# SSD1306_v2_SCH.net
KiCad netlist of a schematic drawn in Altium Designer
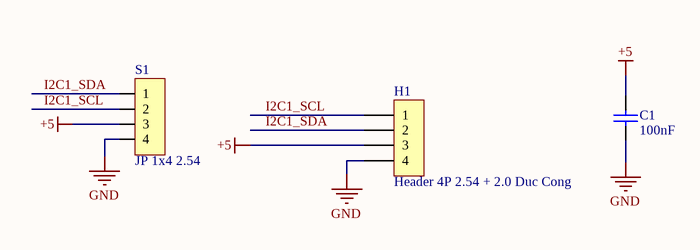
[diagram p0: SSD1306_v2_SCH.SchDoc]

(export (version "E")
  (design (tool "Eeschema 10.0.6"))
  (components
    (comp (ref "C1")
      (value "100nF")
      (footprint "tu 0603")
      (description "Dán")
      (libsource (lib "namnt_Lib") (part "Tu 0603 104 50V 10%"))
    )
    (comp (ref "H1")
      (value "Header 4P 2.54 + 2.0 Duc Cong")
      (footprint "Header 4P DC 2.54 + 2.0")
      (description "Cắm")
      (libsource (lib "namnt_Lib") (part "Header 4P 2.54 + 2.0 Duc Cong"))
    )
    (comp (ref "S1")
      (value "JP 1x4 2.54")
      (footprint "SSD1306_0.96")
      (description "Cắm")
      (libsource (lib "namnt_Lib") (part "SSD1306_0.96"))
    )
  )
  (nets
    (net (code "1") (name "+5") (class "Default")
      (node (ref "C1") (pin "1") (pinfunction "1_1") (pintype "passive"))
      (node (ref "H1") (pin "3") (pinfunction "3_3") (pintype "passive"))
      (node (ref "S1") (pin "3") (pinfunction "3_3") (pintype "passive"))
    )
    (net (code "2") (name "/I2C1_SCL") (class "Default")
      (node (ref "H1") (pin "1") (pinfunction "1_1") (pintype "passive"))
      (node (ref "S1") (pin "2") (pinfunction "2_2") (pintype "passive"))
    )
    (net (code "3") (name "/I2C1_SDA") (class "Default")
      (node (ref "H1") (pin "2") (pinfunction "2_2") (pintype "passive"))
      (node (ref "S1") (pin "1") (pinfunction "1_1") (pintype "passive"))
    )
    (net (code "4") (name "GND") (class "Default")
      (node (ref "C1") (pin "2") (pinfunction "2_2") (pintype "passive"))
      (node (ref "H1") (pin "4") (pinfunction "4_4") (pintype "passive"))
      (node (ref "S1") (pin "4") (pinfunction "4_4") (pintype "passive"))
    )
  )
)
